# RPixel_V1.net
KiCad netlist of a schematic drawn in EAGLE
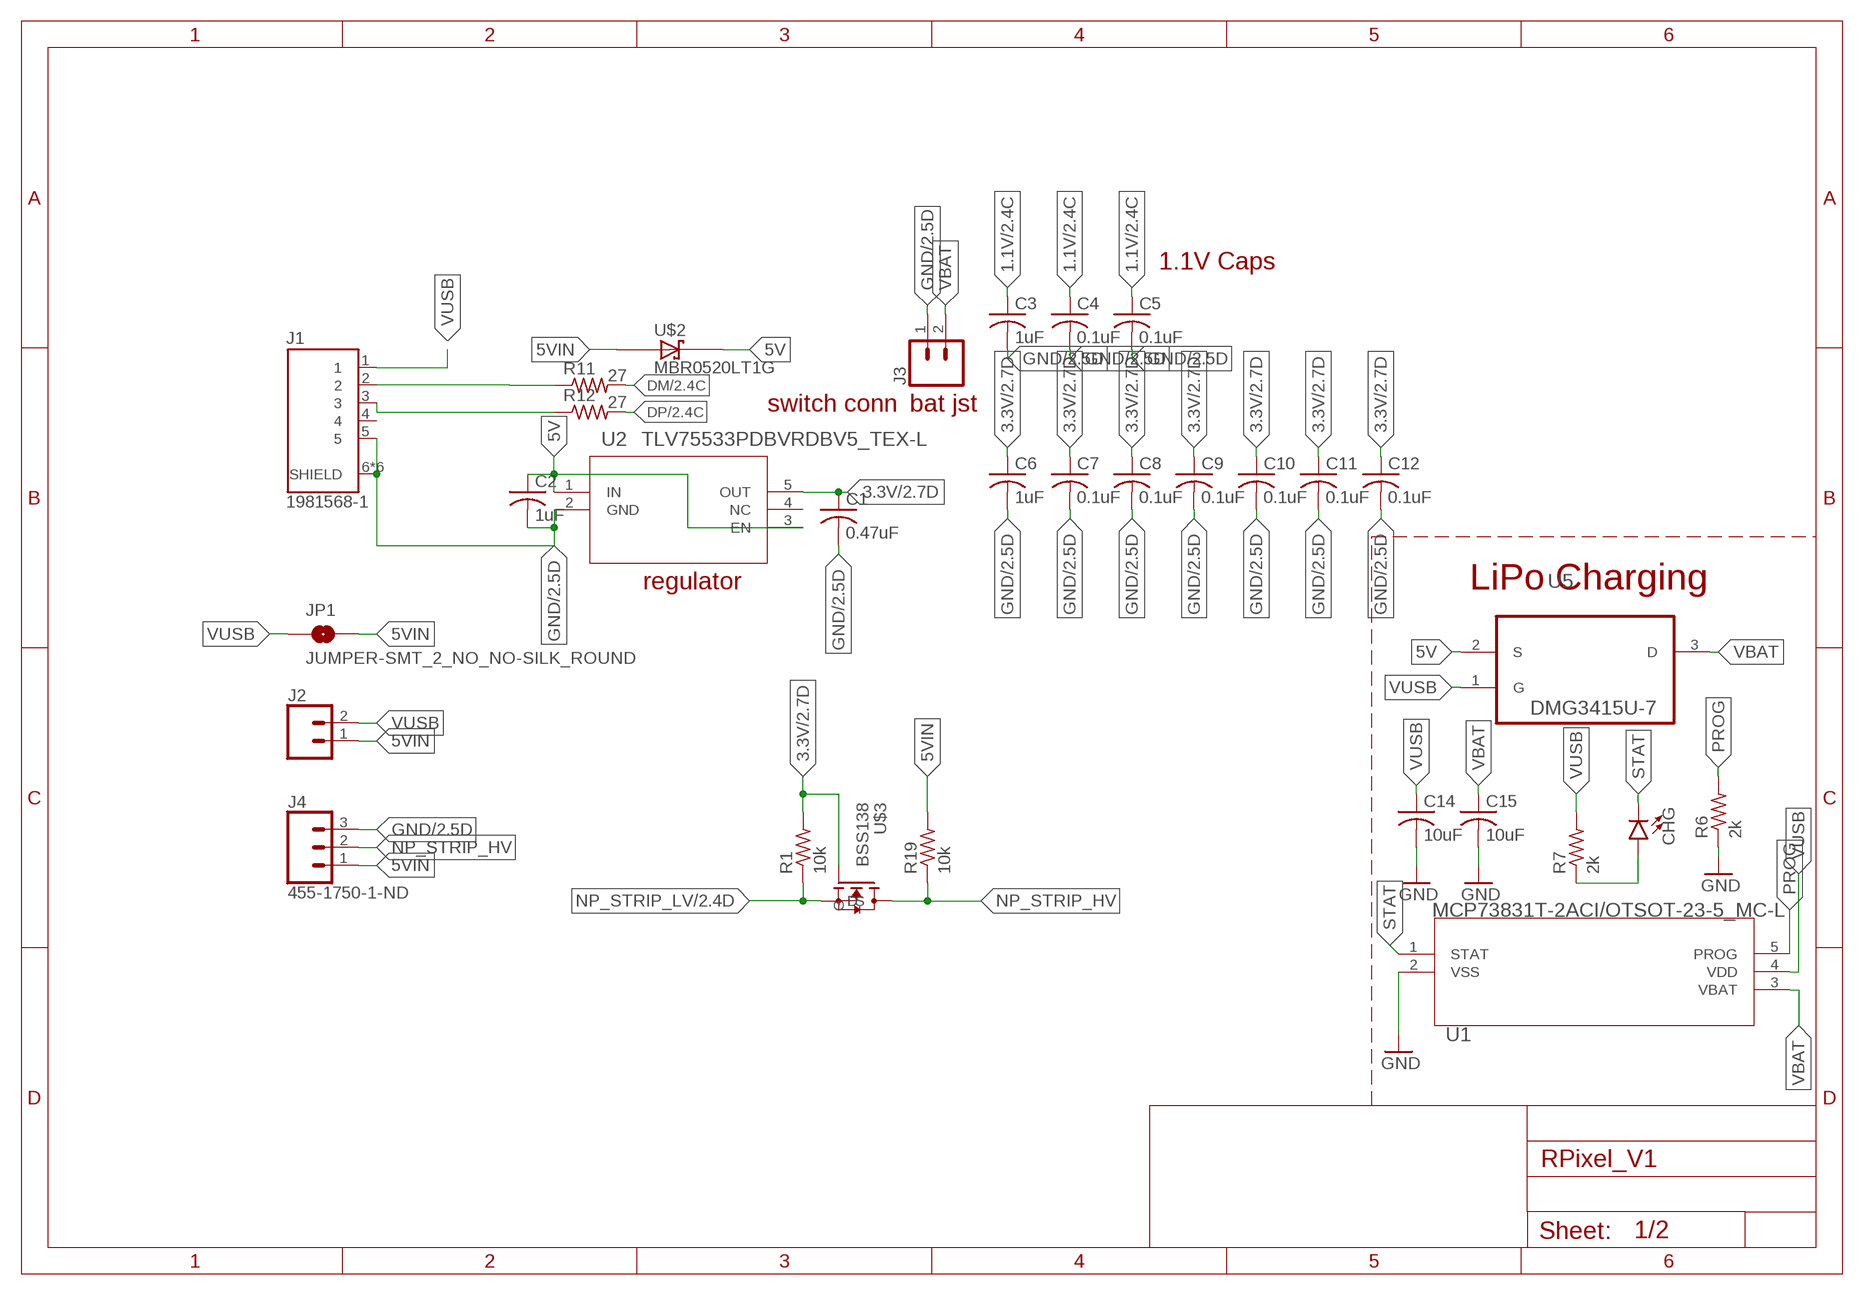
[diagram p0: schematic, sheet 1]
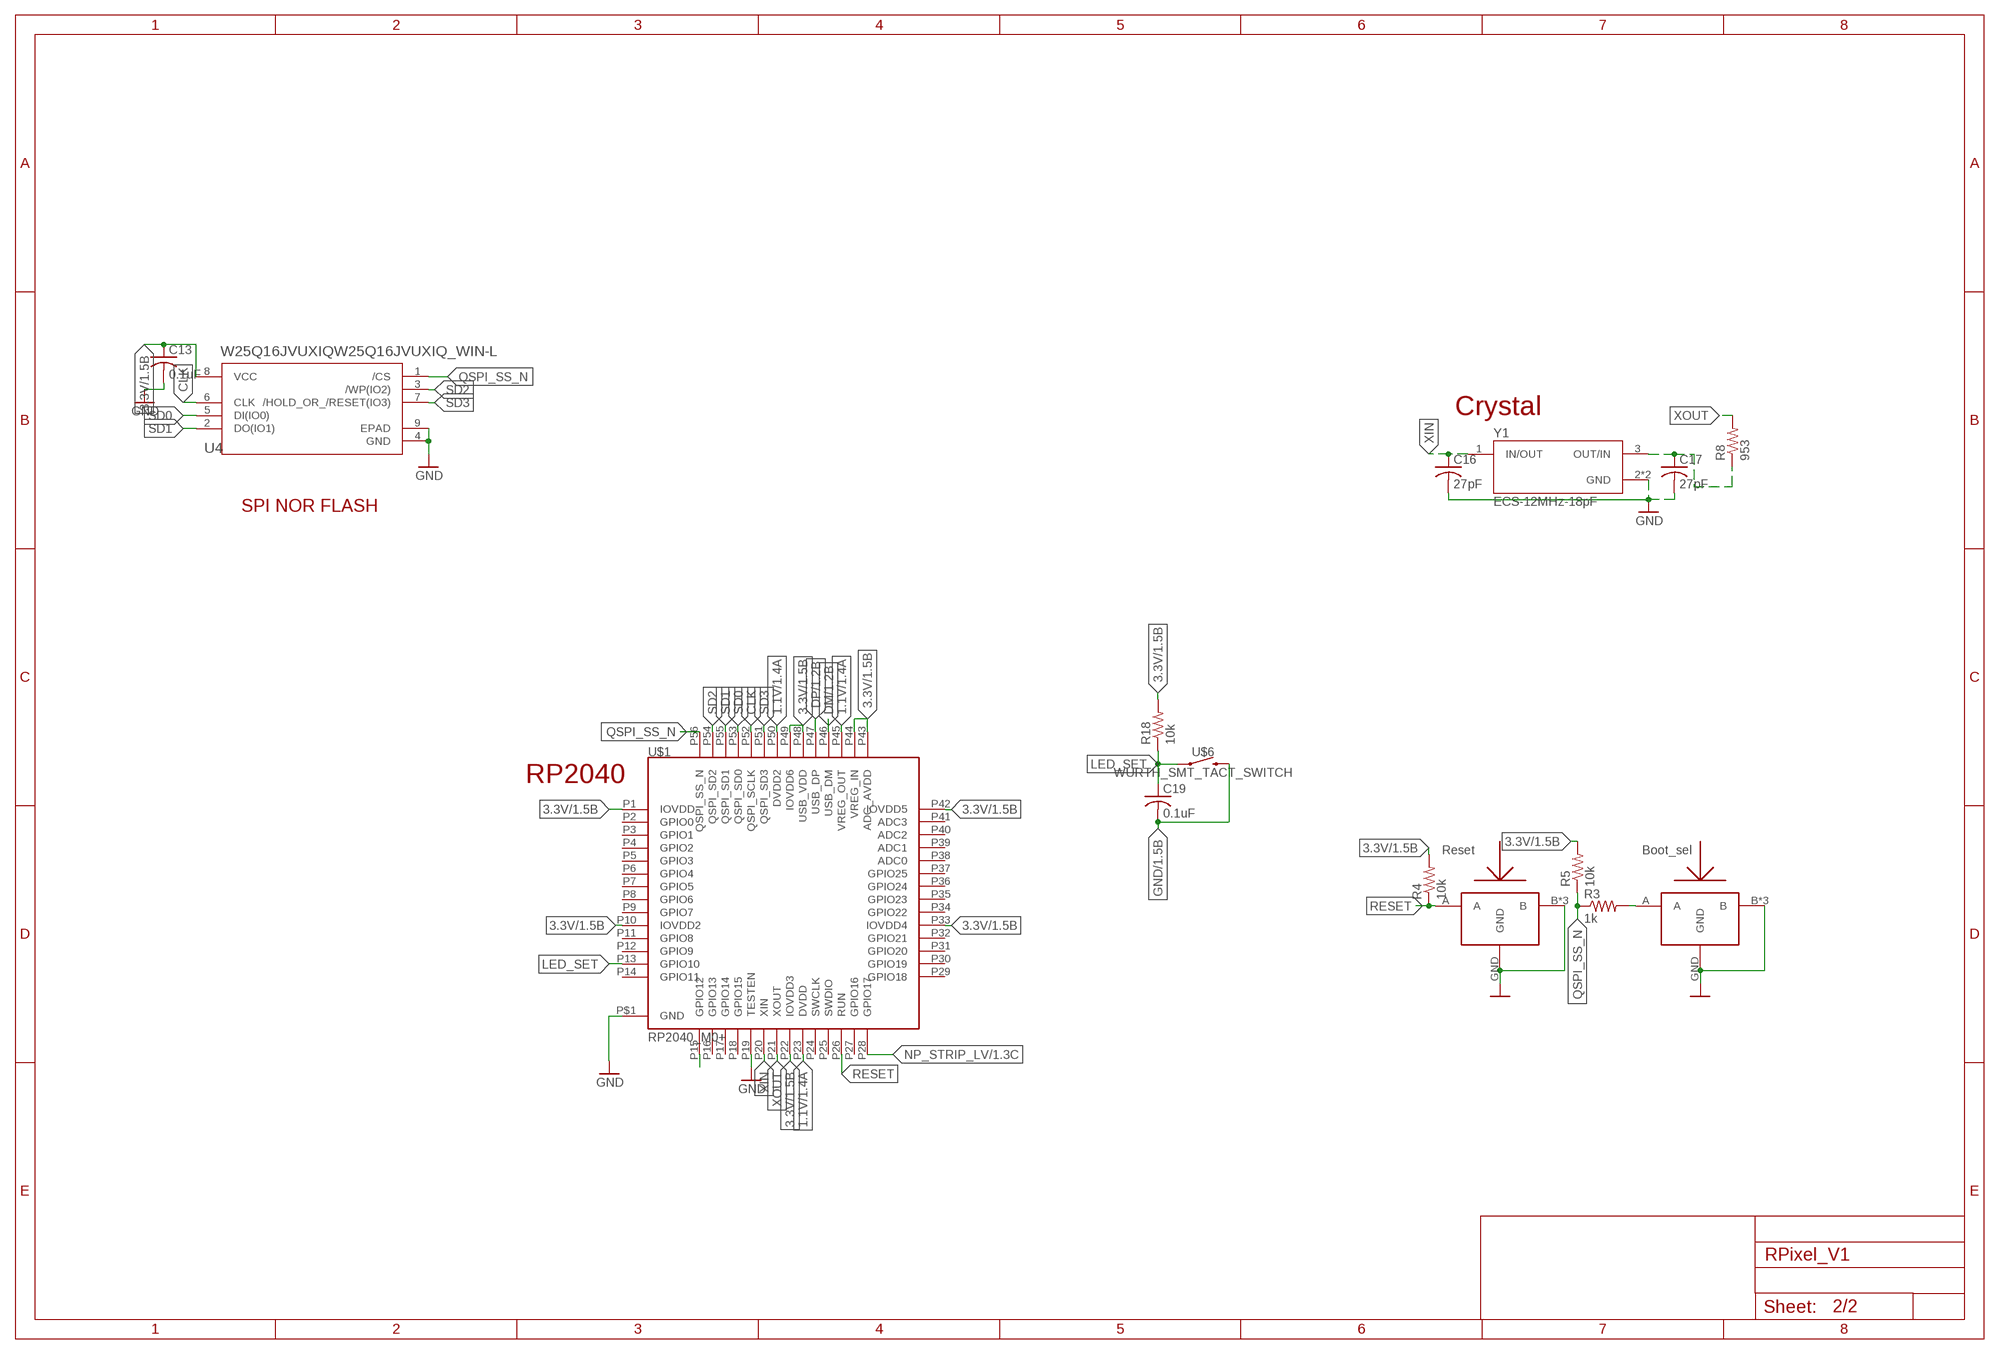
[diagram p1: schematic, sheet 2]

(export (version "E")
  (design (tool "Eeschema 10.0.6"))
  (components
    (comp (ref "C13")
      (value "0.1uF")
      (footprint "eagle-import:C0402")
      (libsource (lib "eagle-import") (part "C-USC0402"))
    )
    (comp (ref "C16")
      (value "27pF")
      (footprint "eagle-import:C0402")
      (libsource (lib "eagle-import") (part "C-USC0402"))
    )
    (comp (ref "C17")
      (value "27pF")
      (footprint "eagle-import:C0402")
      (libsource (lib "eagle-import") (part "C-USC0402"))
    )
    (comp (ref "C19")
      (value "0.1uF")
      (footprint "eagle-import:C0402")
      (libsource (lib "eagle-import") (part "C-USC0402"))
    )
    (comp (ref "R3")
      (value "1k")
      (footprint "eagle-import:R0402")
      (libsource (lib "eagle-import") (part "R-US_R0402"))
    )
    (comp (ref "R4")
      (value "10k")
      (footprint "eagle-import:R0402")
      (libsource (lib "eagle-import") (part "R-US_R0402"))
    )
    (comp (ref "R5")
      (value "10k")
      (footprint "eagle-import:R0402")
      (libsource (lib "eagle-import") (part "R-US_R0402"))
    )
    (comp (ref "R8")
      (value "953")
      (footprint "eagle-import:R0402")
      (libsource (lib "eagle-import") (part "R-US_R0402"))
    )
    (comp (ref "R18")
      (value "10k")
      (footprint "eagle-import:R0402")
      (libsource (lib "eagle-import") (part "R-US_R0402"))
    )
    (comp (ref "U$1")
      (value "RP2040_M0+")
      (footprint "eagle-import:QFN-56")
      (libsource (lib "eagle-import") (part "RP2040_M0+"))
    )
    (comp (ref "U$4")
      (value "SOF-232HST")
      (footprint "eagle-import:3.3X2.9")
      (libsource (lib "eagle-import") (part "SOF-232HST"))
    )
    (comp (ref "U$5")
      (value "SOF-232HST")
      (footprint "eagle-import:3.3X2.9")
      (libsource (lib "eagle-import") (part "SOF-232HST"))
    )
    (comp (ref "U$6")
      (value "WURTH_SMT_TACT_SWITCH")
      (footprint "eagle-import:SIDE_MOUNT_SWITCH")
      (libsource (lib "eagle-import") (part "WURTH_SMT_TACT_SWITCH"))
    )
    (comp (ref "U4")
      (value "W25Q16JVUXIQW25Q16JVUXIQ_WIN-L")
      (footprint "eagle-import:W25Q16JVUXIQ_WIN-L")
      (fields
        (field (name "MANUFACTURER_PART_NUMBER") "W25Q16JVUXIQ")
        (field (name "COPYRIGHT") "Copyright (C) 2018 Accelerated Designs. All rights reserved")
      )
      (libsource (lib "eagle-import") (part "W25Q16JVUXIQW25Q16JVUXIQ_WIN-L"))
    )
    (comp (ref "Y1")
      (value "ECS-12MHz-18pF")
      (footprint "eagle-import:XTAL_ECS-327ATQMV-AS-TR")
      (fields
        (field (name "DIGI-KEY_PART_NUMBER") "XC2826CT-ND")
        (field (name "MF") "ECS Inc.")
        (field (name "MP") "ECS-327ATQMV-AS-TR")
      )
      (libsource (lib "eagle-import") (part "ECS-327ATQMV-AS-TR"))
    )
    (comp (ref "C1")
      (value "0.47uF")
      (footprint "eagle-import:C0805")
      (libsource (lib "eagle-import") (part "C-USC0805"))
    )
    (comp (ref "C2")
      (value "1uF")
      (footprint "eagle-import:C0805")
      (libsource (lib "eagle-import") (part "C-USC0805"))
    )
    (comp (ref "C3")
      (value "1uF")
      (footprint "eagle-import:C0402")
      (libsource (lib "eagle-import") (part "C-USC0402"))
    )
    (comp (ref "C4")
      (value "0.1uF")
      (footprint "eagle-import:C0402")
      (libsource (lib "eagle-import") (part "C-USC0402"))
    )
    (comp (ref "C5")
      (value "0.1uF")
      (footprint "eagle-import:C0402")
      (libsource (lib "eagle-import") (part "C-USC0402"))
    )
    (comp (ref "C6")
      (value "1uF")
      (footprint "eagle-import:C0402")
      (libsource (lib "eagle-import") (part "C-USC0402"))
    )
    (comp (ref "C7")
      (value "0.1uF")
      (footprint "eagle-import:C0402")
      (libsource (lib "eagle-import") (part "C-USC0402"))
    )
    (comp (ref "C8")
      (value "0.1uF")
      (footprint "eagle-import:C0402")
      (libsource (lib "eagle-import") (part "C-USC0402"))
    )
    (comp (ref "C9")
      (value "0.1uF")
      (footprint "eagle-import:C0402")
      (libsource (lib "eagle-import") (part "C-USC0402"))
    )
    (comp (ref "C10")
      (value "0.1uF")
      (footprint "eagle-import:C0402")
      (libsource (lib "eagle-import") (part "C-USC0402"))
    )
    (comp (ref "C11")
      (value "0.1uF")
      (footprint "eagle-import:C0402")
      (libsource (lib "eagle-import") (part "C-USC0402"))
    )
    (comp (ref "C12")
      (value "0.1uF")
      (footprint "eagle-import:C0402")
      (libsource (lib "eagle-import") (part "C-USC0402"))
    )
    (comp (ref "C14")
      (value "10uF")
      (footprint "eagle-import:C0603")
      (libsource (lib "eagle-import") (part "C-USC0603"))
    )
    (comp (ref "C15")
      (value "10uF")
      (footprint "eagle-import:C0603")
      (libsource (lib "eagle-import") (part "C-USC0603"))
    )
    (comp (ref "CHG")
      (value "LED0603")
      (footprint "eagle-import:LED-0603")
      (libsource (lib "eagle-import") (part "LED0603"))
    )
    (comp (ref "J1")
      (value "1981568-1")
      (footprint "eagle-import:TE_1981568-1")
      (fields (field (name "MF") "TE Connectivity") (field (name "MP") "19815681"))
      (libsource (lib "eagle-import") (part "1981568-1"))
    )
    (comp (ref "J2")
      (value "CONN_02")
      (footprint "eagle-import:1X02")
      (libsource (lib "eagle-import") (part "CONN_02"))
    )
    (comp (ref "J3")
      (value "CONN_02-JST-2MM-SMT")
      (footprint "eagle-import:JST-2-SMD")
      (libsource (lib "eagle-import") (part "CONN_02-JST-2MM-SMT"))
    )
    (comp (ref "J4")
      (value "455-1750-1-ND")
      (footprint "eagle-import:1X03")
      (libsource (lib "eagle-import") (part "CONN_03"))
    )
    (comp (ref "JP1")
      (value "JUMPER-SMT_2_NO_NO-SILK_ROUND")
      (footprint "eagle-import:SMT-JUMPER_2_NO_NO-SILK_ROUND")
      (libsource (lib "eagle-import") (part "JUMPER-SMT_2_NO_NO-SILK_ROUND"))
    )
    (comp (ref "R1")
      (value "10k")
      (footprint "eagle-import:R0603")
      (libsource (lib "eagle-import") (part "R-US_R0603"))
    )
    (comp (ref "R6")
      (value "2k")
      (footprint "eagle-import:R0603")
      (libsource (lib "eagle-import") (part "R-US_R0603"))
    )
    (comp (ref "R7")
      (value "2k")
      (footprint "eagle-import:R0603")
      (libsource (lib "eagle-import") (part "R-US_R0603"))
    )
    (comp (ref "R11")
      (value "27")
      (footprint "eagle-import:R0603")
      (libsource (lib "eagle-import") (part "R-US_R0603"))
    )
    (comp (ref "R12")
      (value "27")
      (footprint "eagle-import:R0603")
      (libsource (lib "eagle-import") (part "R-US_R0603"))
    )
    (comp (ref "R19")
      (value "10k")
      (footprint "eagle-import:R0603")
      (libsource (lib "eagle-import") (part "R-US_R0603"))
    )
    (comp (ref "U$2")
      (value "MBR0520LT1G")
      (footprint "eagle-import:SOD3716X117(SOD-123)")
      (fields (field (name "MF") "ON Semiconductor"))
      (libsource (lib "eagle-import") (part "MBR0520LT1G"))
    )
    (comp (ref "U$3")
      (value "BSS138")
      (footprint "eagle-import:BSS138")
      (fields (field (name "MF") "MICROSS/On Semiconductor"))
      (libsource (lib "eagle-import") (part "BSS138"))
    )
    (comp (ref "U1")
      (value "MCP73831T-2ACI/OTSOT-23-5_MC-L")
      (footprint "eagle-import:SOT-23-5_MC-L")
      (fields (field (name "MANUFACTURER_PART_NUMBER") "MCP73831T-2ACI/OT"))
      (libsource (lib "eagle-import") (part "MCP73831T-2ACI/OTSOT-23-5_MC-L"))
    )
    (comp (ref "U2")
      (value "TLV75533PDBVRDBV5_TEX-L")
      (footprint "eagle-import:DBV5_TEX-L")
      (fields
        (field (name "MANUFACTURER_PART_NUMBER") "TLV75533PDBVR")
        (field (name "COPYRIGHT") "Copyright (C) 2018 Accelerated Designs. All rights reserved")
      )
      (libsource (lib "eagle-import") (part "TLV75533PDBVRDBV5_TEX-L"))
    )
    (comp (ref "U5")
      (value "DMG3415U-7")
      (footprint "eagle-import:SOT95P240X105-3N")
      (fields (field (name "MF") "Diodes Inc."))
      (libsource (lib "eagle-import") (part "DMG3415U-7"))
    )
  )
  (nets
    (net (code "1") (name "1.1V") (class "Default")
      (node (ref "C3") (pin "1") (pinfunction "1_1") (pintype "passive"))
      (node (ref "C4") (pin "1") (pinfunction "1_1") (pintype "passive"))
      (node (ref "C5") (pin "1") (pinfunction "1_1") (pintype "passive"))
      (node (ref "U$1") (pin "P23") (pinfunction "DVDD_P23") (pintype "bidirectional"))
      (node (ref "U$1") (pin "P45") (pinfunction "VREG_OUT_P45") (pintype "bidirectional"))
      (node (ref "U$1") (pin "P50") (pinfunction "DVDD2_P50") (pintype "bidirectional"))
    )
    (net (code "2") (name "3.3V") (class "Default")
      (node (ref "C1") (pin "1") (pinfunction "1_1") (pintype "passive"))
      (node (ref "C10") (pin "1") (pinfunction "1_1") (pintype "passive"))
      (node (ref "C11") (pin "1") (pinfunction "1_1") (pintype "passive"))
      (node (ref "C12") (pin "1") (pinfunction "1_1") (pintype "passive"))
      (node (ref "C13") (pin "1") (pinfunction "1_1") (pintype "passive"))
      (node (ref "C6") (pin "1") (pinfunction "1_1") (pintype "passive"))
      (node (ref "C7") (pin "1") (pinfunction "1_1") (pintype "passive"))
      (node (ref "C8") (pin "1") (pinfunction "1_1") (pintype "passive"))
      (node (ref "C9") (pin "1") (pinfunction "1_1") (pintype "passive"))
      (node (ref "R1") (pin "2") (pinfunction "2_2") (pintype "passive"))
      (node (ref "R18") (pin "2") (pinfunction "2_2") (pintype "passive"))
      (node (ref "R4") (pin "2") (pinfunction "2_2") (pintype "passive"))
      (node (ref "R5") (pin "2") (pinfunction "2_2") (pintype "passive"))
      (node (ref "U$1") (pin "P1") (pinfunction "IOVDD_P1") (pintype "bidirectional"))
      (node (ref "U$1") (pin "P10") (pinfunction "IOVDD2_P10") (pintype "bidirectional"))
      (node (ref "U$1") (pin "P22") (pinfunction "IOVDD3_P22") (pintype "bidirectional"))
      (node (ref "U$1") (pin "P33") (pinfunction "IOVDD4_P33") (pintype "bidirectional"))
      (node (ref "U$1") (pin "P42") (pinfunction "IOVDD5_P42") (pintype "bidirectional"))
      (node (ref "U$1") (pin "P43") (pinfunction "ADC_AVDD_P43") (pintype "bidirectional"))
      (node (ref "U$1") (pin "P44") (pinfunction "VREG_IN_P44") (pintype "bidirectional"))
      (node (ref "U$1") (pin "P48") (pinfunction "USB_VDD_P48") (pintype "bidirectional"))
      (node (ref "U$1") (pin "P49") (pinfunction "IOVDD6_P49") (pintype "bidirectional"))
      (node (ref "U$3") (pin "G") (pinfunction "G_G") (pintype "passive"))
      (node (ref "U2") (pin "5") (pinfunction "OUT_5") (pintype "output"))
      (node (ref "U4") (pin "8") (pinfunction "VCC_8") (pintype "passive"))
    )
    (net (code "3") (name "5V") (class "Default")
      (node (ref "C2") (pin "1") (pinfunction "1_1") (pintype "passive"))
      (node (ref "U$2") (pin "1") (pinfunction "C_1") (pintype "passive"))
      (node (ref "U2") (pin "1") (pinfunction "IN_1") (pintype "input"))
      (node (ref "U2") (pin "3") (pinfunction "EN_3") (pintype "input"))
      (node (ref "U5") (pin "2") (pinfunction "S_2") (pintype "passive"))
    )
    (net (code "4") (name "5VIN") (class "Default")
      (node (ref "J2") (pin "1") (pinfunction "1_1") (pintype "passive"))
      (node (ref "J4") (pin "1") (pinfunction "1_1") (pintype "passive"))
      (node (ref "JP1") (pin "2") (pinfunction "2_2") (pintype "passive"))
      (node (ref "R19") (pin "2") (pinfunction "2_2") (pintype "passive"))
      (node (ref "U$2") (pin "2") (pinfunction "A_2") (pintype "passive"))
    )
    (net (code "5") (name "CLK") (class "Default")
      (node (ref "U$1") (pin "P52") (pinfunction "QSPI_SCLK_P52") (pintype "bidirectional"))
      (node (ref "U4") (pin "6") (pinfunction "CLK_6") (pintype "passive"))
    )
    (net (code "6") (name "DM") (class "Default")
      (node (ref "R11") (pin "2") (pinfunction "2_2") (pintype "passive"))
      (node (ref "U$1") (pin "P46") (pinfunction "USB_DM_P46") (pintype "bidirectional"))
    )
    (net (code "7") (name "DP") (class "Default")
      (node (ref "R12") (pin "2") (pinfunction "2_2") (pintype "passive"))
      (node (ref "U$1") (pin "P47") (pinfunction "USB_DP_P47") (pintype "bidirectional"))
    )
    (net (code "8") (name "GND") (class "Default")
      (node (ref "C1") (pin "2") (pinfunction "2_2") (pintype "passive"))
      (node (ref "C10") (pin "2") (pinfunction "2_2") (pintype "passive"))
      (node (ref "C11") (pin "2") (pinfunction "2_2") (pintype "passive"))
      (node (ref "C12") (pin "2") (pinfunction "2_2") (pintype "passive"))
      (node (ref "C13") (pin "2") (pinfunction "2_2") (pintype "passive"))
      (node (ref "C14") (pin "2") (pinfunction "2_2") (pintype "passive"))
      (node (ref "C15") (pin "2") (pinfunction "2_2") (pintype "passive"))
      (node (ref "C16") (pin "2") (pinfunction "2_2") (pintype "passive"))
      (node (ref "C17") (pin "2") (pinfunction "2_2") (pintype "passive"))
      (node (ref "C19") (pin "2") (pinfunction "2_2") (pintype "passive"))
      (node (ref "C2") (pin "2") (pinfunction "2_2") (pintype "passive"))
      (node (ref "C3") (pin "2") (pinfunction "2_2") (pintype "passive"))
      (node (ref "C4") (pin "2") (pinfunction "2_2") (pintype "passive"))
      (node (ref "C5") (pin "2") (pinfunction "2_2") (pintype "passive"))
      (node (ref "C6") (pin "2") (pinfunction "2_2") (pintype "passive"))
      (node (ref "C7") (pin "2") (pinfunction "2_2") (pintype "passive"))
      (node (ref "C8") (pin "2") (pinfunction "2_2") (pintype "passive"))
      (node (ref "C9") (pin "2") (pinfunction "2_2") (pintype "passive"))
      (node (ref "J1") (pin "10") (pinfunction "SHIELD_10") (pintype "passive"))
      (node (ref "J1") (pin "11") (pinfunction "SHIELD_11") (pintype "passive"))
      (node (ref "J1") (pin "5") (pinfunction "5_5") (pintype "passive"))
      (node (ref "J1") (pin "6") (pinfunction "SHIELD_6") (pintype "passive"))
      (node (ref "J1") (pin "7") (pinfunction "SHIELD_7") (pintype "passive"))
      (node (ref "J1") (pin "8") (pinfunction "SHIELD_8") (pintype "passive"))
      (node (ref "J1") (pin "9") (pinfunction "SHIELD_9") (pintype "passive"))
      (node (ref "J3") (pin "1") (pinfunction "2_1") (pintype "passive"))
      (node (ref "J4") (pin "3") (pinfunction "3_3") (pintype "passive"))
      (node (ref "R6") (pin "1") (pinfunction "1_1") (pintype "passive"))
      (node (ref "U$1") (pin "P$1") (pinfunction "GND_P$1") (pintype "bidirectional"))
      (node (ref "U$1") (pin "P19") (pinfunction "TESTEN_P19") (pintype "bidirectional"))
      (node (ref "U$4") (pin "B") (pinfunction "B_B") (pintype "bidirectional"))
      (node (ref "U$4") (pin "B2") (pinfunction "B_B2") (pintype "bidirectional"))
      (node (ref "U$4") (pin "B3") (pinfunction "B_B3") (pintype "bidirectional"))
      (node (ref "U$4") (pin "GND") (pinfunction "GND_GND") (pintype "bidirectional"))
      (node (ref "U$5") (pin "B") (pinfunction "B_B") (pintype "bidirectional"))
      (node (ref "U$5") (pin "B2") (pinfunction "B_B2") (pintype "bidirectional"))
      (node (ref "U$5") (pin "B3") (pinfunction "B_B3") (pintype "bidirectional"))
      (node (ref "U$5") (pin "GND") (pinfunction "GND_GND") (pintype "bidirectional"))
      (node (ref "U$6") (pin "2") (pinfunction "2_2") (pintype "passive"))
      (node (ref "U1") (pin "2") (pinfunction "VSS_2") (pintype "passive"))
      (node (ref "U2") (pin "2") (pinfunction "GND_2") (pintype "power_in"))
      (node (ref "U4") (pin "4") (pinfunction "GND_4") (pintype "passive"))
      (node (ref "U4") (pin "9") (pinfunction "EPAD_9") (pintype "passive"))
      (node (ref "Y1") (pin "2") (pinfunction "GND_2") (pintype "power_in"))
      (node (ref "Y1") (pin "4") (pinfunction "GND_4") (pintype "power_in"))
    )
    (net (code "9") (name "LED_SET") (class "Default")
      (node (ref "C19") (pin "1") (pinfunction "1_1") (pintype "passive"))
      (node (ref "R18") (pin "1") (pinfunction "1_1") (pintype "passive"))
      (node (ref "U$1") (pin "P13") (pinfunction "GPIO10_P13") (pintype "bidirectional"))
      (node (ref "U$6") (pin "1") (pinfunction "1_1") (pintype "passive"))
    )
    (net (code "10") (name "NP_STRIP_HV") (class "Default")
      (node (ref "J4") (pin "2") (pinfunction "2_2") (pintype "passive"))
      (node (ref "R19") (pin "1") (pinfunction "1_1") (pintype "passive"))
      (node (ref "U$3") (pin "D") (pinfunction "D_D") (pintype "passive"))
    )
    (net (code "11") (name "NP_STRIP_LV") (class "Default")
      (node (ref "R1") (pin "1") (pinfunction "1_1") (pintype "passive"))
      (node (ref "U$1") (pin "P28") (pinfunction "GPIO17_P28") (pintype "bidirectional"))
      (node (ref "U$3") (pin "S") (pinfunction "S_S") (pintype "passive"))
    )
    (net (code "12") (name "Net-(CHG-PadA)") (class "Default")
      (node (ref "CHG") (pin "A") (pinfunction "A_A") (pintype "passive"))
      (node (ref "R7") (pin "1") (pinfunction "1_1") (pintype "passive"))
    )
    (net (code "13") (name "Net-(J1-Pad2)") (class "Default")
      (node (ref "J1") (pin "2") (pinfunction "2_2") (pintype "passive"))
      (node (ref "R11") (pin "1") (pinfunction "1_1") (pintype "passive"))
    )
    (net (code "14") (name "Net-(J1-Pad3)") (class "Default")
      (node (ref "J1") (pin "3") (pinfunction "3_3") (pintype "passive"))
      (node (ref "R12") (pin "1") (pinfunction "1_1") (pintype "passive"))
    )
    (net (code "15") (name "Net-(R3-Pad2)") (class "Default")
      (node (ref "R3") (pin "2") (pinfunction "2_2") (pintype "passive"))
      (node (ref "U$5") (pin "A") (pinfunction "A_A") (pintype "bidirectional"))
    )
    (net (code "16") (name "Net-(Y1-OUT{slash}IN)") (class "Default")
      (node (ref "C17") (pin "1") (pinfunction "1_1") (pintype "passive"))
      (node (ref "R8") (pin "1") (pinfunction "1_1") (pintype "passive"))
      (node (ref "Y1") (pin "3") (pinfunction "OUT/IN_3") (pintype "bidirectional"))
    )
    (net (code "17") (name "PROG") (class "Default")
      (node (ref "R6") (pin "2") (pinfunction "2_2") (pintype "passive"))
      (node (ref "U1") (pin "5") (pinfunction "PROG_5") (pintype "passive"))
    )
    (net (code "18") (name "QSPI_SS_N") (class "Default")
      (node (ref "R3") (pin "1") (pinfunction "1_1") (pintype "passive"))
      (node (ref "R5") (pin "1") (pinfunction "1_1") (pintype "passive"))
      (node (ref "U$1") (pin "P56") (pinfunction "QSPI_SS_N_P56") (pintype "bidirectional"))
      (node (ref "U4") (pin "1") (pinfunction "/CS_1") (pintype "passive"))
    )
    (net (code "19") (name "RESET") (class "Default")
      (node (ref "R4") (pin "1") (pinfunction "1_1") (pintype "passive"))
      (node (ref "U$1") (pin "P26") (pinfunction "RUN_P26") (pintype "bidirectional"))
      (node (ref "U$4") (pin "A") (pinfunction "A_A") (pintype "bidirectional"))
    )
    (net (code "20") (name "SD0") (class "Default")
      (node (ref "U$1") (pin "P53") (pinfunction "QSPI_SD0_P53") (pintype "bidirectional"))
      (node (ref "U4") (pin "5") (pinfunction "DI(IO0)_5") (pintype "passive"))
    )
    (net (code "21") (name "SD1") (class "Default")
      (node (ref "U$1") (pin "P55") (pinfunction "QSPI_SD1_P55") (pintype "bidirectional"))
      (node (ref "U4") (pin "2") (pinfunction "DO(IO1)_2") (pintype "passive"))
    )
    (net (code "22") (name "SD2") (class "Default")
      (node (ref "U$1") (pin "P54") (pinfunction "QSPI_SD2_P54") (pintype "bidirectional"))
      (node (ref "U4") (pin "3") (pinfunction "/WP(IO2)_3") (pintype "passive"))
    )
    (net (code "23") (name "SD3") (class "Default")
      (node (ref "U$1") (pin "P51") (pinfunction "QSPI_SD3_P51") (pintype "bidirectional"))
      (node (ref "U4") (pin "7") (pinfunction "/HOLD_OR_/RESET(IO3)_7") (pintype "passive"))
    )
    (net (code "24") (name "STAT") (class "Default")
      (node (ref "CHG") (pin "C") (pinfunction "C_C") (pintype "passive"))
      (node (ref "U1") (pin "1") (pinfunction "STAT_1") (pintype "passive"))
    )
    (net (code "25") (name "VBAT") (class "Default")
      (node (ref "C15") (pin "1") (pinfunction "1_1") (pintype "passive"))
      (node (ref "J3") (pin "2") (pinfunction "1_2") (pintype "passive"))
      (node (ref "U1") (pin "3") (pinfunction "VBAT_3") (pintype "passive"))
      (node (ref "U5") (pin "3") (pinfunction "D_3") (pintype "output"))
    )
    (net (code "26") (name "VUSB") (class "Default")
      (node (ref "C14") (pin "1") (pinfunction "1_1") (pintype "passive"))
      (node (ref "J1") (pin "1") (pinfunction "1_1") (pintype "passive"))
      (node (ref "J2") (pin "2") (pinfunction "2_2") (pintype "passive"))
      (node (ref "JP1") (pin "1") (pinfunction "1_1") (pintype "passive"))
      (node (ref "R7") (pin "2") (pinfunction "2_2") (pintype "passive"))
      (node (ref "U1") (pin "4") (pinfunction "VDD_4") (pintype "passive"))
      (node (ref "U5") (pin "1") (pinfunction "G_1") (pintype "power_in"))
    )
    (net (code "27") (name "XIN") (class "Default")
      (node (ref "C16") (pin "1") (pinfunction "1_1") (pintype "passive"))
      (node (ref "U$1") (pin "P20") (pinfunction "XIN_P20") (pintype "bidirectional"))
      (node (ref "Y1") (pin "1") (pinfunction "IN/OUT_1") (pintype "bidirectional"))
    )
    (net (code "28") (name "XOUT") (class "Default")
      (node (ref "R8") (pin "2") (pinfunction "2_2") (pintype "passive"))
      (node (ref "U$1") (pin "P21") (pinfunction "XOUT_P21") (pintype "bidirectional"))
    )
    (net (code "29") (name "unconnected-(J1-Pad4)") (class "Default")
      (node (ref "J1") (pin "4") (pinfunction "4_4") (pintype "passive"))
    )
    (net (code "30") (name "unconnected-(U$1-ADC0-PadP38)") (class "Default")
      (node (ref "U$1") (pin "P38") (pinfunction "ADC0_P38") (pintype "bidirectional"))
    )
    (net (code "31") (name "unconnected-(U$1-ADC1-PadP39)") (class "Default")
      (node (ref "U$1") (pin "P39") (pinfunction "ADC1_P39") (pintype "bidirectional"))
    )
    (net (code "32") (name "unconnected-(U$1-ADC2-PadP40)") (class "Default")
      (node (ref "U$1") (pin "P40") (pinfunction "ADC2_P40") (pintype "bidirectional"))
    )
    (net (code "33") (name "unconnected-(U$1-ADC3-PadP41)") (class "Default")
      (node (ref "U$1") (pin "P41") (pinfunction "ADC3_P41") (pintype "bidirectional"))
    )
    (net (code "34") (name "unconnected-(U$1-GPIO0-PadP2)") (class "Default")
      (node (ref "U$1") (pin "P2") (pinfunction "GPIO0_P2") (pintype "bidirectional"))
    )
    (net (code "35") (name "unconnected-(U$1-GPIO1-PadP3)") (class "Default")
      (node (ref "U$1") (pin "P3") (pinfunction "GPIO1_P3") (pintype "bidirectional"))
    )
    (net (code "36") (name "unconnected-(U$1-GPIO2-PadP4)") (class "Default")
      (node (ref "U$1") (pin "P4") (pinfunction "GPIO2_P4") (pintype "bidirectional"))
    )
    (net (code "37") (name "unconnected-(U$1-GPIO3-PadP5)") (class "Default")
      (node (ref "U$1") (pin "P5") (pinfunction "GPIO3_P5") (pintype "bidirectional"))
    )
    (net (code "38") (name "unconnected-(U$1-GPIO4-PadP6)") (class "Default")
      (node (ref "U$1") (pin "P6") (pinfunction "GPIO4_P6") (pintype "bidirectional"))
    )
    (net (code "39") (name "unconnected-(U$1-GPIO5-PadP7)") (class "Default")
      (node (ref "U$1") (pin "P7") (pinfunction "GPIO5_P7") (pintype "bidirectional"))
    )
    (net (code "40") (name "unconnected-(U$1-GPIO6-PadP8)") (class "Default")
      (node (ref "U$1") (pin "P8") (pinfunction "GPIO6_P8") (pintype "bidirectional"))
    )
    (net (code "41") (name "unconnected-(U$1-GPIO7-PadP9)") (class "Default")
      (node (ref "U$1") (pin "P9") (pinfunction "GPIO7_P9") (pintype "bidirectional"))
    )
    (net (code "42") (name "unconnected-(U$1-GPIO8-PadP11)") (class "Default")
      (node (ref "U$1") (pin "P11") (pinfunction "GPIO8_P11") (pintype "bidirectional"))
    )
    (net (code "43") (name "unconnected-(U$1-GPIO9-PadP12)") (class "Default")
      (node (ref "U$1") (pin "P12") (pinfunction "GPIO9_P12") (pintype "bidirectional"))
    )
    (net (code "44") (name "unconnected-(U$1-GPIO11-PadP14)") (class "Default")
      (node (ref "U$1") (pin "P14") (pinfunction "GPIO11_P14") (pintype "bidirectional"))
    )
    (net (code "45") (name "unconnected-(U$1-GPIO12-PadP15)") (class "Default")
      (node (ref "U$1") (pin "P15") (pinfunction "GPIO12_P15") (pintype "bidirectional"))
    )
    (net (code "46") (name "unconnected-(U$1-GPIO13-PadP16)") (class "Default")
      (node (ref "U$1") (pin "P16") (pinfunction "GPIO13_P16") (pintype "bidirectional"))
    )
    (net (code "47") (name "unconnected-(U$1-GPIO14-PadP17)") (class "Default")
      (node (ref "U$1") (pin "P17") (pinfunction "GPIO14_P17") (pintype "bidirectional"))
    )
    (net (code "48") (name "unconnected-(U$1-GPIO15-PadP18)") (class "Default")
      (node (ref "U$1") (pin "P18") (pinfunction "GPIO15_P18") (pintype "bidirectional"))
    )
    (net (code "49") (name "unconnected-(U$1-GPIO16-PadP27)") (class "Default")
      (node (ref "U$1") (pin "P27") (pinfunction "GPIO16_P27") (pintype "bidirectional"))
    )
    (net (code "50") (name "unconnected-(U$1-GPIO18-PadP29)") (class "Default")
      (node (ref "U$1") (pin "P29") (pinfunction "GPIO18_P29") (pintype "bidirectional"))
    )
    (net (code "51") (name "unconnected-(U$1-GPIO19-PadP30)") (class "Default")
      (node (ref "U$1") (pin "P30") (pinfunction "GPIO19_P30") (pintype "bidirectional"))
    )
    (net (code "52") (name "unconnected-(U$1-GPIO20-PadP31)") (class "Default")
      (node (ref "U$1") (pin "P31") (pinfunction "GPIO20_P31") (pintype "bidirectional"))
    )
    (net (code "53") (name "unconnected-(U$1-GPIO21-PadP32)") (class "Default")
      (node (ref "U$1") (pin "P32") (pinfunction "GPIO21_P32") (pintype "bidirectional"))
    )
    (net (code "54") (name "unconnected-(U$1-GPIO22-PadP34)") (class "Default")
      (node (ref "U$1") (pin "P34") (pinfunction "GPIO22_P34") (pintype "bidirectional"))
    )
    (net (code "55") (name "unconnected-(U$1-GPIO23-PadP35)") (class "Default")
      (node (ref "U$1") (pin "P35") (pinfunction "GPIO23_P35") (pintype "bidirectional"))
    )
    (net (code "56") (name "unconnected-(U$1-GPIO24-PadP36)") (class "Default")
      (node (ref "U$1") (pin "P36") (pinfunction "GPIO24_P36") (pintype "bidirectional"))
    )
    (net (code "57") (name "unconnected-(U$1-GPIO25-PadP37)") (class "Default")
      (node (ref "U$1") (pin "P37") (pinfunction "GPIO25_P37") (pintype "bidirectional"))
    )
    (net (code "58") (name "unconnected-(U$1-SWCLK-PadP24)") (class "Default")
      (node (ref "U$1") (pin "P24") (pinfunction "SWCLK_P24") (pintype "bidirectional"))
    )
    (net (code "59") (name "unconnected-(U$1-SWDIO-PadP25)") (class "Default")
      (node (ref "U$1") (pin "P25") (pinfunction "SWDIO_P25") (pintype "bidirectional"))
    )
    (net (code "60") (name "unconnected-(U2-NC-Pad4)") (class "Default")
      (node (ref "U2") (pin "4") (pinfunction "NC_4") (pintype "no_connect"))
    )
  )
)
